# security-accelerometer.net
KiCad netlist of a schematic drawn in Altium Designer
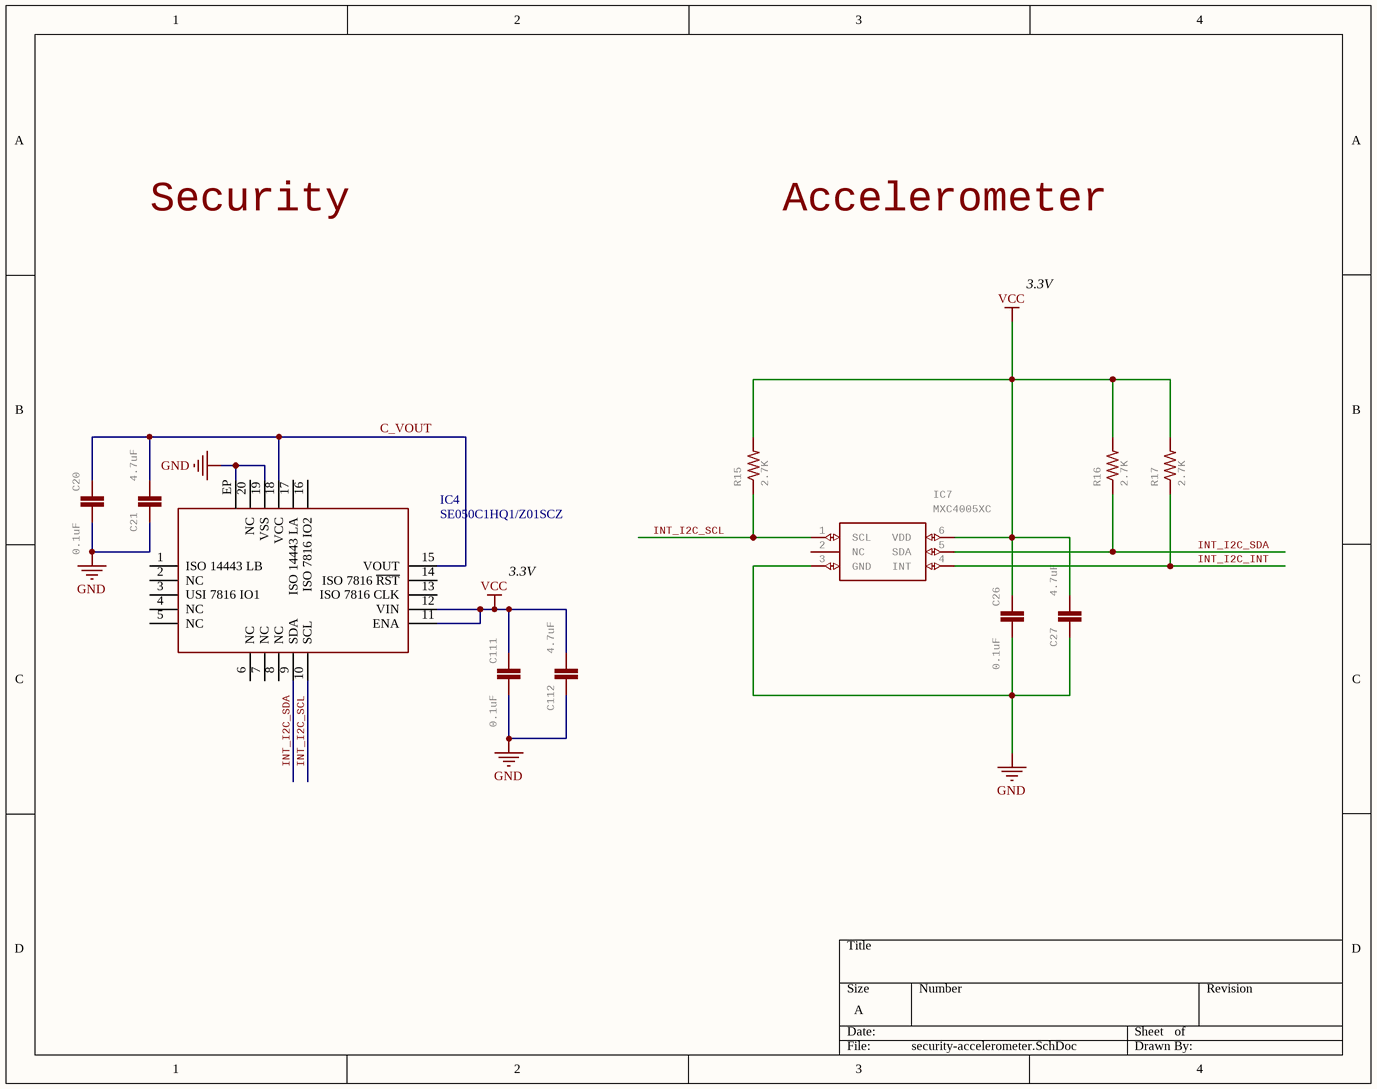
[diagram p0: security-accelerometer.SchDoc]

(export (version "E")
  (design (tool "Eeschema 10.0.6"))
  (components
    (comp (ref "C20")
      (value "0.1uF")
      (footprint "0402-CAP")
      (description "CAPACITOR, European symbol")
      (fields (field (name "MPN") "C0402C104Z4VAC"))
      (libsource (lib "rt10") (part "C-EUC0201"))
    )
    (comp (ref "C21")
      (value "4.7uF")
      (footprint "0402-CAP")
      (description "CapacitorStandard 0603 ceramic capacitor, and 0.1\" leaded capacitor.")
      (fields (field (name "MPN") "JMK105BBJ475MV-F"))
      (libsource (lib "rt10") (part "CAP0402-CAP"))
    )
    (comp (ref "C26")
      (value "0.1uF")
      (footprint "0402-CAP")
      (description "CAPACITOR, European symbol")
      (fields (field (name "MPN") "C0402C104Z4VAC"))
      (libsource (lib "rt10") (part "C-EUC0201"))
    )
    (comp (ref "C27")
      (value "4.7uF")
      (footprint "0402-CAP")
      (description "CapacitorStandard 0603 ceramic capacitor, and 0.1\" leaded capacitor.")
      (fields (field (name "MPN") "JMK105BBJ475MV-F"))
      (libsource (lib "rt10") (part "CAP0402-CAP"))
    )
    (comp (ref "C111")
      (value "0.1uF")
      (footprint "0402-CAP")
      (description "CAPACITOR, European symbol")
      (fields (field (name "MPN") "C0402C104Z4VAC"))
      (libsource (lib "rt10") (part "C-EUC0201"))
    )
    (comp (ref "C112")
      (value "4.7uF")
      (footprint "0402-CAP")
      (description "CapacitorStandard 0603 ceramic capacitor, and 0.1\" leaded capacitor.")
      (fields (field (name "MPN") "JMK105BBJ475MV-F"))
      (libsource (lib "rt10") (part "CAP0402-CAP"))
    )
    (comp (ref "IC4")
      (value "SE050C1HQ1/Z01SCZ")
      (footprint "HX2QFN20")
      (libsource (lib "rt10") (part "SE050C1HQ1/Z01SCZ"))
    )
    (comp (ref "IC7")
      (value "MXC4005XC")
      (footprint "MXC4005XC")
      (description "Accelerometers Monolithic and Wafer Level Packaged Three-Axis Accelerometer   Source:  Datasheet")
      (fields (field (name "MOUSER_PART_NUMBER") "438-MXC4005XC"))
      (libsource (lib "rt10") (part "MXC4005XC"))
    )
    (comp (ref "R15")
      (value "2.7K")
      (footprint "0402-RES")
      (description "ResistorBasic schematic elements and footprints for 0603, 1206, and PTH resistors.")
      (fields (field (name "MPN") "AC0402JR-072K7L"))
      (libsource (lib "rt10") (part "RESISTOR0402-RES"))
    )
    (comp (ref "R16")
      (value "2.7K")
      (footprint "0402-RES")
      (description "ResistorBasic schematic elements and footprints for 0603, 1206, and PTH resistors.")
      (fields (field (name "MPN") "AC0402JR-072K7L"))
      (libsource (lib "rt10") (part "RESISTOR0402-RES"))
    )
    (comp (ref "R17")
      (value "2.7K")
      (footprint "0402-RES")
      (description "ResistorBasic schematic elements and footprints for 0603, 1206, and PTH resistors.")
      (fields (field (name "MPN") "AC0402JR-072K7L"))
      (libsource (lib "rt10") (part "RESISTOR0402-RES"))
    )
  )
  (nets
    (net (code "1") (name "/C_VOUT") (class "Default")
      (node (ref "C20") (pin "1") (pinfunction "1_1") (pintype "passive"))
      (node (ref "C21") (pin "2") (pinfunction "2_2") (pintype "passive"))
      (node (ref "IC4") (pin "15") (pinfunction "VOUT_15") (pintype "passive"))
      (node (ref "IC4") (pin "18") (pinfunction "VCC_18") (pintype "passive"))
    )
    (net (code "2") (name "/INT_I2C_INT") (class "Default")
      (node (ref "IC7") (pin "4") (pinfunction "INT_4") (pintype "bidirectional"))
      (node (ref "R17") (pin "1") (pinfunction "1_1") (pintype "passive"))
    )
    (net (code "3") (name "/INT_I2C_SCL") (class "Default")
      (node (ref "IC4") (pin "10") (pinfunction "SCL_10") (pintype "passive"))
      (node (ref "IC7") (pin "1") (pinfunction "SCL_1") (pintype "bidirectional"))
      (node (ref "R15") (pin "1") (pinfunction "1_1") (pintype "passive"))
    )
    (net (code "4") (name "/INT_I2C_SDA") (class "Default")
      (node (ref "IC4") (pin "9") (pinfunction "SDA_9") (pintype "passive"))
      (node (ref "IC7") (pin "5") (pinfunction "SDA_5") (pintype "bidirectional"))
      (node (ref "R16") (pin "1") (pinfunction "1_1") (pintype "passive"))
    )
    (net (code "5") (name "GND") (class "Default")
      (node (ref "C111") (pin "2") (pinfunction "2_2") (pintype "passive"))
      (node (ref "C112") (pin "1") (pinfunction "1_1") (pintype "passive"))
      (node (ref "C20") (pin "2") (pinfunction "2_2") (pintype "passive"))
      (node (ref "C21") (pin "1") (pinfunction "1_1") (pintype "passive"))
      (node (ref "C26") (pin "2") (pinfunction "2_2") (pintype "passive"))
      (node (ref "C27") (pin "1") (pinfunction "1_1") (pintype "passive"))
      (node (ref "IC4") (pin "19") (pinfunction "VSS_19") (pintype "passive"))
      (node (ref "IC4") (pin "EP") (pinfunction "EP_EP") (pintype "passive"))
      (node (ref "IC7") (pin "3") (pinfunction "GND_3") (pintype "bidirectional"))
    )
    (net (code "6") (name "VCC") (class "Default")
      (node (ref "C111") (pin "1") (pinfunction "1_1") (pintype "passive"))
      (node (ref "C112") (pin "2") (pinfunction "2_2") (pintype "passive"))
      (node (ref "C26") (pin "1") (pinfunction "1_1") (pintype "passive"))
      (node (ref "C27") (pin "2") (pinfunction "2_2") (pintype "passive"))
      (node (ref "IC4") (pin "11") (pinfunction "ENA_11") (pintype "passive"))
      (node (ref "IC4") (pin "12") (pinfunction "VIN_12") (pintype "passive"))
      (node (ref "IC7") (pin "6") (pinfunction "VDD_6") (pintype "bidirectional"))
      (node (ref "R15") (pin "2") (pinfunction "2_2") (pintype "passive"))
      (node (ref "R16") (pin "2") (pinfunction "2_2") (pintype "passive"))
      (node (ref "R17") (pin "2") (pinfunction "2_2") (pintype "passive"))
    )
    (net (code "7") (name "unconnected-(IC4-ISO_7816_CLK-Pad13)") (class "Default")
      (node (ref "IC4") (pin "13") (pinfunction "ISO_7816_CLK_13") (pintype "passive"))
    )
    (net (code "8") (name "unconnected-(IC4-ISO_7816_IO2-Pad16)") (class "Default")
      (node (ref "IC4") (pin "16") (pinfunction "ISO_7816_IO2_16") (pintype "passive"))
    )
    (net (code "9") (name "unconnected-(IC4-ISO_7816_~{RST}-Pad14)") (class "Default")
      (node (ref "IC4") (pin "14") (pinfunction "ISO_7816_~{RST}_14") (pintype "passive"))
    )
    (net (code "10") (name "unconnected-(IC4-ISO_14443_LA-Pad17)") (class "Default")
      (node (ref "IC4") (pin "17") (pinfunction "ISO_14443_LA_17") (pintype "passive"))
    )
    (net (code "11") (name "unconnected-(IC4-ISO_14443_LB-Pad1)") (class "Default")
      (node (ref "IC4") (pin "1") (pinfunction "ISO_14443_LB_1") (pintype "passive"))
    )
    (net (code "12") (name "unconnected-(IC4-NC-Pad2)") (class "Default")
      (node (ref "IC4") (pin "2") (pinfunction "NC_2") (pintype "passive"))
    )
    (net (code "13") (name "unconnected-(IC4-NC-Pad4)") (class "Default")
      (node (ref "IC4") (pin "4") (pinfunction "NC_4") (pintype "passive"))
    )
    (net (code "14") (name "unconnected-(IC4-NC-Pad5)") (class "Default")
      (node (ref "IC4") (pin "5") (pinfunction "NC_5") (pintype "passive"))
    )
    (net (code "15") (name "unconnected-(IC4-NC-Pad6)") (class "Default")
      (node (ref "IC4") (pin "6") (pinfunction "NC_6") (pintype "passive"))
    )
    (net (code "16") (name "unconnected-(IC4-NC-Pad7)") (class "Default")
      (node (ref "IC4") (pin "7") (pinfunction "NC_7") (pintype "passive"))
    )
    (net (code "17") (name "unconnected-(IC4-NC-Pad8)") (class "Default")
      (node (ref "IC4") (pin "8") (pinfunction "NC_8") (pintype "passive"))
    )
    (net (code "18") (name "unconnected-(IC4-NC-Pad20)") (class "Default")
      (node (ref "IC4") (pin "20") (pinfunction "NC_20") (pintype "passive"))
    )
    (net (code "19") (name "unconnected-(IC4-USI_7816_IO1-Pad3)") (class "Default")
      (node (ref "IC4") (pin "3") (pinfunction "USI_7816_IO1_3") (pintype "passive"))
    )
    (net (code "20") (name "unconnected-(IC7-NC-Pad2)") (class "Default")
      (node (ref "IC7") (pin "2") (pinfunction "NC_2") (pintype "passive"))
    )
  )
)
